# LM317.net
KiCad netlist of a schematic drawn in EAGLE
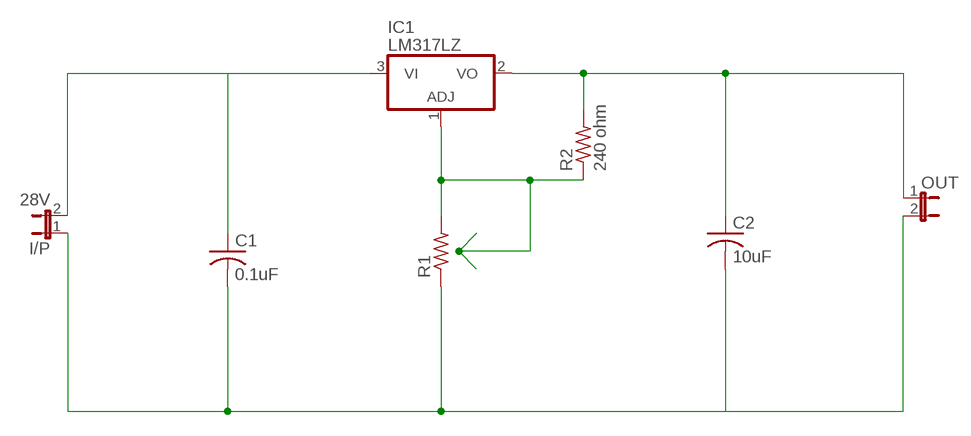
[diagram p0: schematic, sheet 1]

(export (version "E")
  (design (tool "Eeschema 10.0.6"))
  (components
    (comp (ref "C1")
      (value "0.1uF")
      (footprint "eagle-import:C025-025X050")
      (libsource (lib "eagle-import") (part "C-US025-025X050"))
    )
    (comp (ref "C2")
      (value "10uF")
      (footprint "eagle-import:C025-025X050")
      (libsource (lib "eagle-import") (part "C-US025-025X050"))
    )
    (comp (ref "I/P")
      (value "28V")
      (footprint "eagle-import:JP1")
      (libsource (lib "eagle-import") (part "JP1E"))
    )
    (comp (ref "IC1")
      (value "LM317LZ")
      (footprint "eagle-import:TO92")
      (libsource (lib "eagle-import") (part "317LZLM"))
    )
    (comp (ref "OUT")
      (value "JP1E")
      (footprint "eagle-import:JP1")
      (libsource (lib "eagle-import") (part "JP1E"))
    )
    (comp (ref "R1")
      (value "R-US_0204/7")
      (footprint "eagle-import:0204_7")
      (libsource (lib "eagle-import") (part "R-US_0204/7"))
    )
    (comp (ref "R2")
      (value "240 ohm")
      (footprint "eagle-import:0204_7")
      (libsource (lib "eagle-import") (part "R-US_0204/7"))
    )
  )
  (nets
    (net (code "1") (name "Net-(C1-Pad2)") (class "Default")
      (node (ref "C1") (pin "2") (pinfunction "2_2") (pintype "passive"))
      (node (ref "C2") (pin "2") (pinfunction "2_2") (pintype "passive"))
      (node (ref "I/P") (pin "1") (pinfunction "1_1") (pintype "passive"))
      (node (ref "OUT") (pin "2") (pinfunction "2_2") (pintype "passive"))
      (node (ref "R1") (pin "1") (pinfunction "1_1") (pintype "passive"))
    )
    (net (code "2") (name "Net-(IC1-ADJ)") (class "Default")
      (node (ref "IC1") (pin "1") (pinfunction "ADJ_1") (pintype "input"))
      (node (ref "R1") (pin "2") (pinfunction "2_2") (pintype "passive"))
      (node (ref "R2") (pin "1") (pinfunction "1_1") (pintype "passive"))
    )
    (net (code "3") (name "Net-(IC1-VI)") (class "Default")
      (node (ref "C1") (pin "1") (pinfunction "1_1") (pintype "passive"))
      (node (ref "I/P") (pin "2") (pinfunction "2_2") (pintype "passive"))
      (node (ref "IC1") (pin "3") (pinfunction "VI_3") (pintype "input"))
    )
    (net (code "4") (name "Net-(IC1-VO)") (class "Default")
      (node (ref "C2") (pin "1") (pinfunction "1_1") (pintype "passive"))
      (node (ref "IC1") (pin "2") (pinfunction "VO_2") (pintype "passive"))
      (node (ref "OUT") (pin "1") (pinfunction "1_1") (pintype "passive"))
      (node (ref "R2") (pin "2") (pinfunction "2_2") (pintype "passive"))
    )
  )
)
